# LineCliffSensors.net
KiCad netlist of a schematic drawn in Altium Designer
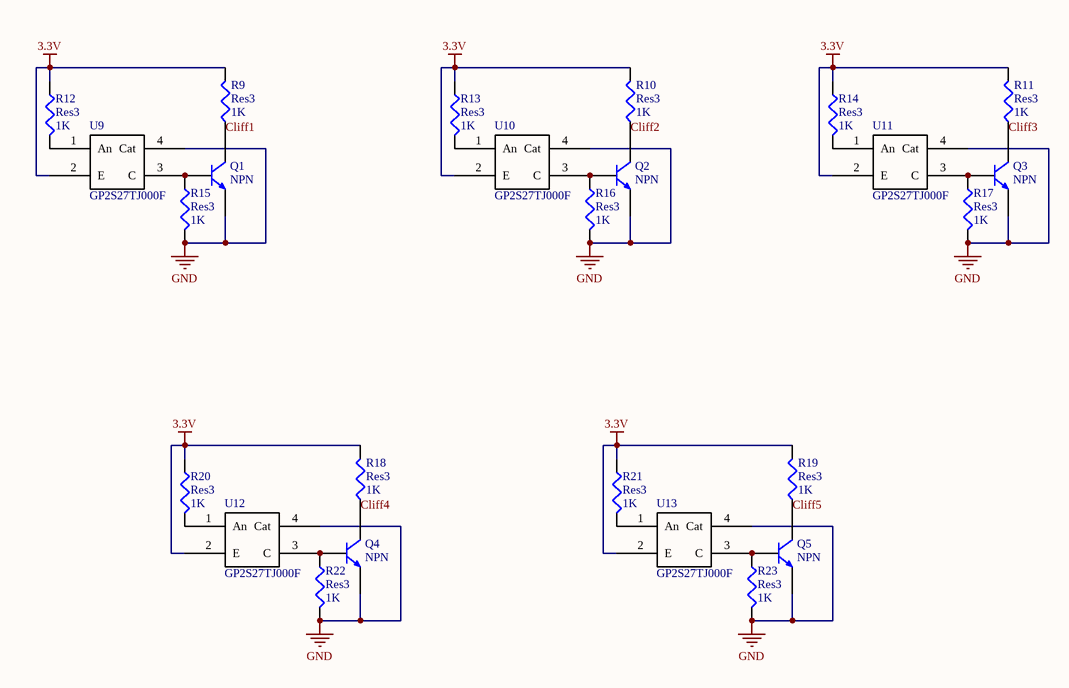
[diagram p0: LineCliffSensors.SchDoc]

(export (version "E")
  (design (tool "Eeschema 10.0.6"))
  (components
    (comp (ref "Q1") (value "NPN") (footprint "SOT-23") (libsource (lib "mrone") (part "NPN")))
    (comp (ref "Q2") (value "NPN") (footprint "SOT-23") (libsource (lib "mrone") (part "NPN")))
    (comp (ref "Q3") (value "NPN") (footprint "SOT-23") (libsource (lib "mrone") (part "NPN")))
    (comp (ref "Q4") (value "NPN") (footprint "SOT-23") (libsource (lib "mrone") (part "NPN")))
    (comp (ref "Q5") (value "NPN") (footprint "SOT-23") (libsource (lib "mrone") (part "NPN")))
    (comp (ref "R9")
      (value "Res3")
      (footprint "RESC1608L")
      (description "Resistor")
      (fields (field (name "ALTIUM_VALUE") "1K") (field (name "PUBLISHER") "Altium Limited"))
      (libsource (lib "Miscellaneous Devices") (part "Res3"))
    )
    (comp (ref "R10")
      (value "Res3")
      (footprint "RESC1608L")
      (description "Resistor")
      (fields (field (name "ALTIUM_VALUE") "1K") (field (name "PUBLISHER") "Altium Limited"))
      (libsource (lib "Miscellaneous Devices") (part "Res3"))
    )
    (comp (ref "R11")
      (value "Res3")
      (footprint "RESC1608L")
      (description "Resistor")
      (fields (field (name "ALTIUM_VALUE") "1K") (field (name "PUBLISHER") "Altium Limited"))
      (libsource (lib "Miscellaneous Devices") (part "Res3"))
    )
    (comp (ref "R12")
      (value "Res3")
      (footprint "RESC1608L")
      (description "Resistor")
      (fields (field (name "ALTIUM_VALUE") "1K") (field (name "PUBLISHER") "Altium Limited"))
      (libsource (lib "Miscellaneous Devices") (part "Res3"))
    )
    (comp (ref "R13")
      (value "Res3")
      (footprint "RESC1608L")
      (description "Resistor")
      (fields (field (name "ALTIUM_VALUE") "1K") (field (name "PUBLISHER") "Altium Limited"))
      (libsource (lib "Miscellaneous Devices") (part "Res3"))
    )
    (comp (ref "R14")
      (value "Res3")
      (footprint "RESC1608L")
      (description "Resistor")
      (fields (field (name "ALTIUM_VALUE") "1K") (field (name "PUBLISHER") "Altium Limited"))
      (libsource (lib "Miscellaneous Devices") (part "Res3"))
    )
    (comp (ref "R15")
      (value "Res3")
      (footprint "RESC1608L")
      (description "Resistor")
      (fields (field (name "ALTIUM_VALUE") "1K") (field (name "PUBLISHER") "Altium Limited"))
      (libsource (lib "Miscellaneous Devices") (part "Res3"))
    )
    (comp (ref "R16")
      (value "Res3")
      (footprint "RESC1608L")
      (description "Resistor")
      (fields (field (name "ALTIUM_VALUE") "1K") (field (name "PUBLISHER") "Altium Limited"))
      (libsource (lib "Miscellaneous Devices") (part "Res3"))
    )
    (comp (ref "R17")
      (value "Res3")
      (footprint "RESC1608L")
      (description "Resistor")
      (fields (field (name "ALTIUM_VALUE") "1K") (field (name "PUBLISHER") "Altium Limited"))
      (libsource (lib "Miscellaneous Devices") (part "Res3"))
    )
    (comp (ref "R18")
      (value "Res3")
      (footprint "RESC1608L")
      (description "Resistor")
      (fields (field (name "ALTIUM_VALUE") "1K") (field (name "PUBLISHER") "Altium Limited"))
      (libsource (lib "Miscellaneous Devices") (part "Res3"))
    )
    (comp (ref "R19")
      (value "Res3")
      (footprint "RESC1608L")
      (description "Resistor")
      (fields (field (name "ALTIUM_VALUE") "1K") (field (name "PUBLISHER") "Altium Limited"))
      (libsource (lib "Miscellaneous Devices") (part "Res3"))
    )
    (comp (ref "R20")
      (value "Res3")
      (footprint "RESC1608L")
      (description "Resistor")
      (fields (field (name "ALTIUM_VALUE") "1K") (field (name "PUBLISHER") "Altium Limited"))
      (libsource (lib "Miscellaneous Devices") (part "Res3"))
    )
    (comp (ref "R21")
      (value "Res3")
      (footprint "RESC1608L")
      (description "Resistor")
      (fields (field (name "ALTIUM_VALUE") "1K") (field (name "PUBLISHER") "Altium Limited"))
      (libsource (lib "Miscellaneous Devices") (part "Res3"))
    )
    (comp (ref "R22")
      (value "Res3")
      (footprint "RESC1608L")
      (description "Resistor")
      (fields (field (name "ALTIUM_VALUE") "1K") (field (name "PUBLISHER") "Altium Limited"))
      (libsource (lib "Miscellaneous Devices") (part "Res3"))
    )
    (comp (ref "R23")
      (value "Res3")
      (footprint "RESC1608L")
      (description "Resistor")
      (fields (field (name "ALTIUM_VALUE") "1K") (field (name "PUBLISHER") "Altium Limited"))
      (libsource (lib "Miscellaneous Devices") (part "Res3"))
    )
    (comp (ref "U9")
      (value "GP2S27TJ000F")
      (footprint "GP2S27J0000F")
      (libsource (lib "mrone") (part "GP2S27TJ000F"))
    )
    (comp (ref "U10")
      (value "GP2S27TJ000F")
      (footprint "GP2S27J0000F")
      (libsource (lib "mrone") (part "GP2S27TJ000F"))
    )
    (comp (ref "U11")
      (value "GP2S27TJ000F")
      (footprint "GP2S27J0000F")
      (libsource (lib "mrone") (part "GP2S27TJ000F"))
    )
    (comp (ref "U12")
      (value "GP2S27TJ000F")
      (footprint "GP2S27J0000F")
      (libsource (lib "mrone") (part "GP2S27TJ000F"))
    )
    (comp (ref "U13")
      (value "GP2S27TJ000F")
      (footprint "GP2S27J0000F")
      (libsource (lib "mrone") (part "GP2S27TJ000F"))
    )
  )
  (nets
    (net (code "1") (name "/Cliff1") (class "Default")
      (node (ref "Q1") (pin "3") (pinfunction "C_3") (pintype "passive"))
      (node (ref "R9") (pin "1") (pinfunction "1_1") (pintype "passive"))
    )
    (net (code "2") (name "/Cliff2") (class "Default")
      (node (ref "Q2") (pin "3") (pinfunction "C_3") (pintype "passive"))
      (node (ref "R10") (pin "1") (pinfunction "1_1") (pintype "passive"))
    )
    (net (code "3") (name "/Cliff3") (class "Default")
      (node (ref "Q3") (pin "3") (pinfunction "C_3") (pintype "passive"))
      (node (ref "R11") (pin "1") (pinfunction "1_1") (pintype "passive"))
    )
    (net (code "4") (name "/Cliff4") (class "Default")
      (node (ref "Q4") (pin "3") (pinfunction "C_3") (pintype "passive"))
      (node (ref "R18") (pin "1") (pinfunction "1_1") (pintype "passive"))
    )
    (net (code "5") (name "/Cliff5") (class "Default")
      (node (ref "Q5") (pin "3") (pinfunction "C_3") (pintype "passive"))
      (node (ref "R19") (pin "1") (pinfunction "1_1") (pintype "passive"))
    )
    (net (code "6") (name "3.3V") (class "Default")
      (node (ref "R10") (pin "2") (pinfunction "2_2") (pintype "passive"))
      (node (ref "R11") (pin "2") (pinfunction "2_2") (pintype "passive"))
      (node (ref "R12") (pin "1") (pinfunction "1_1") (pintype "passive"))
      (node (ref "R13") (pin "1") (pinfunction "1_1") (pintype "passive"))
      (node (ref "R14") (pin "1") (pinfunction "1_1") (pintype "passive"))
      (node (ref "R18") (pin "2") (pinfunction "2_2") (pintype "passive"))
      (node (ref "R19") (pin "2") (pinfunction "2_2") (pintype "passive"))
      (node (ref "R20") (pin "1") (pinfunction "1_1") (pintype "passive"))
      (node (ref "R21") (pin "1") (pinfunction "1_1") (pintype "passive"))
      (node (ref "R9") (pin "2") (pinfunction "2_2") (pintype "passive"))
      (node (ref "U10") (pin "2") (pinfunction "E_2") (pintype "passive"))
      (node (ref "U11") (pin "2") (pinfunction "E_2") (pintype "passive"))
      (node (ref "U12") (pin "2") (pinfunction "E_2") (pintype "passive"))
      (node (ref "U13") (pin "2") (pinfunction "E_2") (pintype "passive"))
      (node (ref "U9") (pin "2") (pinfunction "E_2") (pintype "passive"))
    )
    (net (code "7") (name "GND") (class "Default")
      (node (ref "Q1") (pin "2") (pinfunction "E_2") (pintype "passive"))
      (node (ref "Q2") (pin "2") (pinfunction "E_2") (pintype "passive"))
      (node (ref "Q3") (pin "2") (pinfunction "E_2") (pintype "passive"))
      (node (ref "Q4") (pin "2") (pinfunction "E_2") (pintype "passive"))
      (node (ref "Q5") (pin "2") (pinfunction "E_2") (pintype "passive"))
      (node (ref "R15") (pin "2") (pinfunction "2_2") (pintype "passive"))
      (node (ref "R16") (pin "2") (pinfunction "2_2") (pintype "passive"))
      (node (ref "R17") (pin "2") (pinfunction "2_2") (pintype "passive"))
      (node (ref "R22") (pin "2") (pinfunction "2_2") (pintype "passive"))
      (node (ref "R23") (pin "2") (pinfunction "2_2") (pintype "passive"))
      (node (ref "U10") (pin "4") (pinfunction "Cat_4") (pintype "passive"))
      (node (ref "U11") (pin "4") (pinfunction "Cat_4") (pintype "passive"))
      (node (ref "U12") (pin "4") (pinfunction "Cat_4") (pintype "passive"))
      (node (ref "U13") (pin "4") (pinfunction "Cat_4") (pintype "passive"))
      (node (ref "U9") (pin "4") (pinfunction "Cat_4") (pintype "passive"))
    )
    (net (code "8") (name "Net-(Q1-B)") (class "Default")
      (node (ref "Q1") (pin "1") (pinfunction "B_1") (pintype "passive"))
      (node (ref "R15") (pin "1") (pinfunction "1_1") (pintype "passive"))
      (node (ref "U9") (pin "3") (pinfunction "C_3") (pintype "passive"))
    )
    (net (code "9") (name "Net-(Q2-B)") (class "Default")
      (node (ref "Q2") (pin "1") (pinfunction "B_1") (pintype "passive"))
      (node (ref "R16") (pin "1") (pinfunction "1_1") (pintype "passive"))
      (node (ref "U10") (pin "3") (pinfunction "C_3") (pintype "passive"))
    )
    (net (code "10") (name "Net-(Q3-B)") (class "Default")
      (node (ref "Q3") (pin "1") (pinfunction "B_1") (pintype "passive"))
      (node (ref "R17") (pin "1") (pinfunction "1_1") (pintype "passive"))
      (node (ref "U11") (pin "3") (pinfunction "C_3") (pintype "passive"))
    )
    (net (code "11") (name "Net-(Q4-B)") (class "Default")
      (node (ref "Q4") (pin "1") (pinfunction "B_1") (pintype "passive"))
      (node (ref "R22") (pin "1") (pinfunction "1_1") (pintype "passive"))
      (node (ref "U12") (pin "3") (pinfunction "C_3") (pintype "passive"))
    )
    (net (code "12") (name "Net-(Q5-B)") (class "Default")
      (node (ref "Q5") (pin "1") (pinfunction "B_1") (pintype "passive"))
      (node (ref "R23") (pin "1") (pinfunction "1_1") (pintype "passive"))
      (node (ref "U13") (pin "3") (pinfunction "C_3") (pintype "passive"))
    )
    (net (code "13") (name "Net-(U9-An)") (class "Default")
      (node (ref "R12") (pin "2") (pinfunction "2_2") (pintype "passive"))
      (node (ref "U9") (pin "1") (pinfunction "An_1") (pintype "passive"))
    )
    (net (code "14") (name "Net-(U10-An)") (class "Default")
      (node (ref "R13") (pin "2") (pinfunction "2_2") (pintype "passive"))
      (node (ref "U10") (pin "1") (pinfunction "An_1") (pintype "passive"))
    )
    (net (code "15") (name "Net-(U11-An)") (class "Default")
      (node (ref "R14") (pin "2") (pinfunction "2_2") (pintype "passive"))
      (node (ref "U11") (pin "1") (pinfunction "An_1") (pintype "passive"))
    )
    (net (code "16") (name "Net-(U12-An)") (class "Default")
      (node (ref "R20") (pin "2") (pinfunction "2_2") (pintype "passive"))
      (node (ref "U12") (pin "1") (pinfunction "An_1") (pintype "passive"))
    )
    (net (code "17") (name "Net-(U13-An)") (class "Default")
      (node (ref "R21") (pin "2") (pinfunction "2_2") (pintype "passive"))
      (node (ref "U13") (pin "1") (pinfunction "An_1") (pintype "passive"))
    )
  )
)
